# Esquema.net
KiCad netlist of a schematic drawn in EAGLE
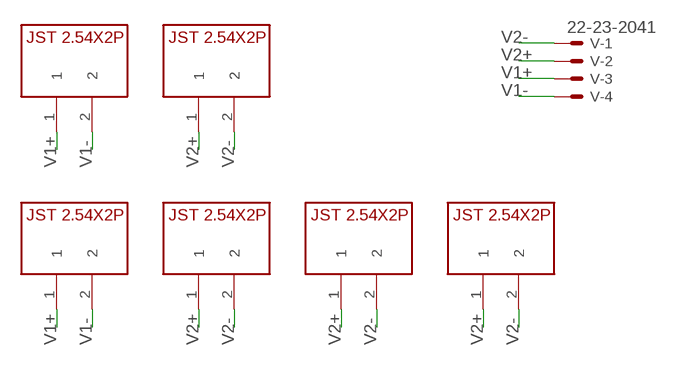
[diagram p0: schematic, sheet 1]

(export (version "E")
  (design (tool "Eeschema 10.0.6"))
  (components
    (comp (ref "U$1")
      (value "JST2.54X2P")
      (footprint "eagle-import:JST2.54X2P_FOOTPRINT")
      (libsource (lib "eagle-import") (part "JST2.54X2P"))
    )
    (comp (ref "U$2")
      (value "JST2.54X2P")
      (footprint "eagle-import:JST2.54X2P_FOOTPRINT")
      (libsource (lib "eagle-import") (part "JST2.54X2P"))
    )
    (comp (ref "U$3")
      (value "JST2.54X2P")
      (footprint "eagle-import:JST2.54X2P_FOOTPRINT")
      (libsource (lib "eagle-import") (part "JST2.54X2P"))
    )
    (comp (ref "U$4")
      (value "JST2.54X2P")
      (footprint "eagle-import:JST2.54X2P_FOOTPRINT")
      (libsource (lib "eagle-import") (part "JST2.54X2P"))
    )
    (comp (ref "U$5")
      (value "JST2.54X2P")
      (footprint "eagle-import:JST2.54X2P_FOOTPRINT")
      (libsource (lib "eagle-import") (part "JST2.54X2P"))
    )
    (comp (ref "U$6")
      (value "JST2.54X2P")
      (footprint "eagle-import:JST2.54X2P_FOOTPRINT")
      (libsource (lib "eagle-import") (part "JST2.54X2P"))
    )
    (comp (ref "V")
      (value "22-23-2041")
      (footprint "eagle-import:22-23-2041")
      (fields (field (name "MF") "MOLEX"))
      (libsource (lib "eagle-import") (part "22-23-2041"))
    )
  )
  (nets
    (net (code "1") (name "/V1+") (class "Default")
      (node (ref "U$1") (pin "1") (pinfunction "1_1") (pintype "bidirectional"))
      (node (ref "U$4") (pin "1") (pinfunction "1_1") (pintype "bidirectional"))
      (node (ref "V") (pin "3") (pinfunction "S_3") (pintype "passive"))
    )
    (net (code "2") (name "/V1-") (class "Default")
      (node (ref "U$1") (pin "2") (pinfunction "2_2") (pintype "bidirectional"))
      (node (ref "U$4") (pin "2") (pinfunction "2_2") (pintype "bidirectional"))
      (node (ref "V") (pin "4") (pinfunction "S_4") (pintype "passive"))
    )
    (net (code "3") (name "/V2+") (class "Default")
      (node (ref "U$2") (pin "1") (pinfunction "1_1") (pintype "bidirectional"))
      (node (ref "U$3") (pin "1") (pinfunction "1_1") (pintype "bidirectional"))
      (node (ref "U$5") (pin "1") (pinfunction "1_1") (pintype "bidirectional"))
      (node (ref "U$6") (pin "1") (pinfunction "1_1") (pintype "bidirectional"))
      (node (ref "V") (pin "2") (pinfunction "S_2") (pintype "passive"))
    )
    (net (code "4") (name "/V2-") (class "Default")
      (node (ref "U$2") (pin "2") (pinfunction "2_2") (pintype "bidirectional"))
      (node (ref "U$3") (pin "2") (pinfunction "2_2") (pintype "bidirectional"))
      (node (ref "U$5") (pin "2") (pinfunction "2_2") (pintype "bidirectional"))
      (node (ref "U$6") (pin "2") (pinfunction "2_2") (pintype "bidirectional"))
      (node (ref "V") (pin "1") (pinfunction "S_1") (pintype "passive"))
    )
  )
)
